# Detectielus_schema.net
KiCad netlist of a schematic drawn in EAGLE
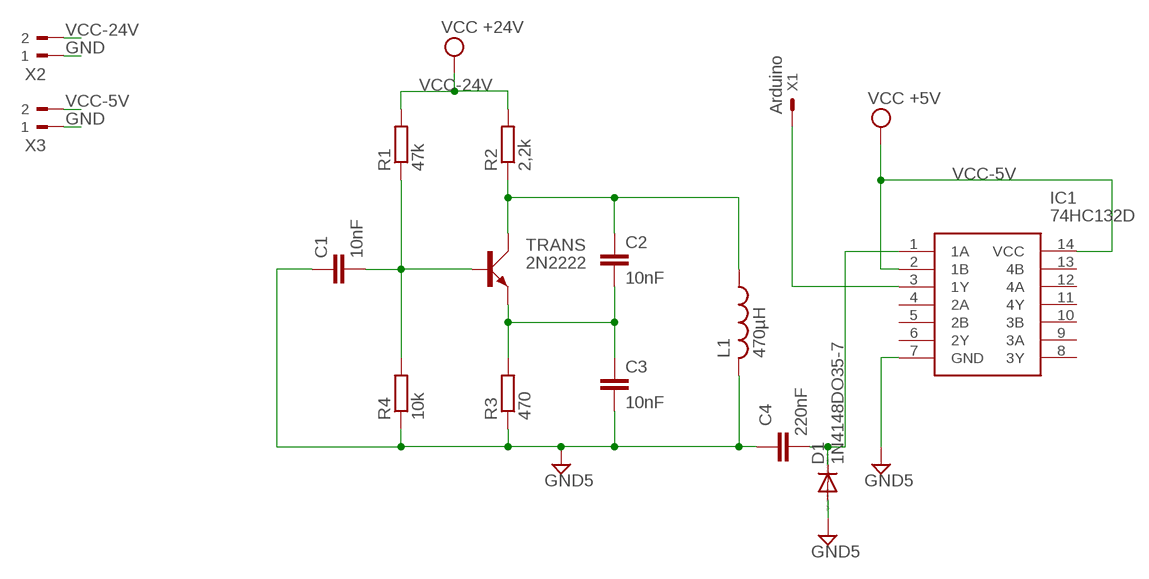
[diagram p0: schematic, sheet 1]

(export (version "E")
  (design (tool "Eeschema 10.0.6"))
  (components
    (comp (ref "C1")
      (value "10nF")
      (footprint "eagle-import:C050-024X044")
      (libsource (lib "eagle-import") (part "CAPACITOR"))
    )
    (comp (ref "C2")
      (value "10nF")
      (footprint "eagle-import:C050-024X044")
      (libsource (lib "eagle-import") (part "CAPACITOR"))
    )
    (comp (ref "C3")
      (value "10nF")
      (footprint "eagle-import:C050-024X044")
      (libsource (lib "eagle-import") (part "CAPACITOR"))
    )
    (comp (ref "C4")
      (value "220nF")
      (footprint "eagle-import:C050-024X044")
      (libsource (lib "eagle-import") (part "CAPACITOR"))
    )
    (comp (ref "D1")
      (value "1N4148DO35-7")
      (footprint "eagle-import:DO35-7")
      (libsource (lib "eagle-import") (part "1N4148DO35-7"))
    )
    (comp (ref "IC1")
      (value "74HC132D")
      (footprint "eagle-import:SOIC127P600X175-14N")
      (fields (field (name "RS_PART_NUMBER") "4367408"))
      (libsource (lib "eagle-import") (part "74HC132D"))
    )
    (comp (ref "L1")
      (value "470µH")
      (footprint "eagle-import:IR-4")
      (libsource (lib "eagle-import") (part "SPOEL"))
    )
    (comp (ref "R1")
      (value "47k")
      (footprint "eagle-import:RDH_15")
      (libsource (lib "eagle-import") (part "RESISTOR"))
    )
    (comp (ref "R2")
      (value "2,2k")
      (footprint "eagle-import:RDH_15")
      (libsource (lib "eagle-import") (part "RESISTOR"))
    )
    (comp (ref "R3")
      (value "470")
      (footprint "eagle-import:RDH_15")
      (libsource (lib "eagle-import") (part "RESISTOR"))
    )
    (comp (ref "R4")
      (value "10k")
      (footprint "eagle-import:RDH_15")
      (libsource (lib "eagle-import") (part "RESISTOR"))
    )
    (comp (ref "TRANS")
      (value "2N2222")
      (footprint "eagle-import:TO220AV")
      (libsource (lib "eagle-import") (part "TIP41C"))
    )
    (comp (ref "X1")
      (value "Arduino")
      (footprint "eagle-import:332-02")
      (libsource (lib "eagle-import") (part "332-02"))
    )
    (comp (ref "X2")
      (value "90-2")
      (footprint "eagle-import:90-2")
      (libsource (lib "eagle-import") (part "90-2"))
    )
    (comp (ref "X3")
      (value "90-2")
      (footprint "eagle-import:90-2")
      (libsource (lib "eagle-import") (part "90-2"))
    )
  )
  (nets
    (net (code "1") (name "/GND") (class "Default")
      (node (ref "X2") (pin "1") (pinfunction "1_1") (pintype "passive"))
      (node (ref "X3") (pin "1") (pinfunction "1_1") (pintype "passive"))
    )
    (net (code "2") (name "GND5") (class "Default")
      (node (ref "C1") (pin "1") (pinfunction "1_1") (pintype "passive"))
      (node (ref "C3") (pin "2") (pinfunction "2_2") (pintype "passive"))
      (node (ref "C4") (pin "1") (pinfunction "1_1") (pintype "passive"))
      (node (ref "D1") (pin "A") (pinfunction "A_A") (pintype "passive"))
      (node (ref "IC1") (pin "7") (pinfunction "GND_7") (pintype "power_in"))
      (node (ref "L1") (pin "2") (pinfunction "2_2") (pintype "passive"))
      (node (ref "R3") (pin "1") (pinfunction "1_1") (pintype "passive"))
      (node (ref "R4") (pin "1") (pinfunction "1_1") (pintype "passive"))
    )
    (net (code "3") (name "Net-(C1-Pad2)") (class "Default")
      (node (ref "C1") (pin "2") (pinfunction "2_2") (pintype "passive"))
      (node (ref "R1") (pin "1") (pinfunction "1_1") (pintype "passive"))
      (node (ref "R4") (pin "2") (pinfunction "2_2") (pintype "passive"))
      (node (ref "TRANS") (pin "B") (pinfunction "B_B") (pintype "passive"))
    )
    (net (code "4") (name "Net-(C2-Pad1)") (class "Default")
      (node (ref "C2") (pin "1") (pinfunction "1_1") (pintype "passive"))
      (node (ref "L1") (pin "1") (pinfunction "1_1") (pintype "passive"))
      (node (ref "R2") (pin "1") (pinfunction "1_1") (pintype "passive"))
      (node (ref "TRANS") (pin "C") (pinfunction "C_C") (pintype "passive"))
    )
    (net (code "5") (name "Net-(C2-Pad2)") (class "Default")
      (node (ref "C2") (pin "2") (pinfunction "2_2") (pintype "passive"))
      (node (ref "C3") (pin "1") (pinfunction "1_1") (pintype "passive"))
      (node (ref "R3") (pin "2") (pinfunction "2_2") (pintype "passive"))
      (node (ref "TRANS") (pin "E") (pinfunction "E_E") (pintype "passive"))
    )
    (net (code "6") (name "Net-(IC1-1A)") (class "Default")
      (node (ref "C4") (pin "2") (pinfunction "2_2") (pintype "passive"))
      (node (ref "D1") (pin "C") (pinfunction "C_C") (pintype "passive"))
      (node (ref "IC1") (pin "1") (pinfunction "1A_1") (pintype "bidirectional"))
    )
    (net (code "7") (name "Net-(IC1-1Y)") (class "Default")
      (node (ref "IC1") (pin "3") (pinfunction "1Y_3") (pintype "bidirectional"))
      (node (ref "X1") (pin "1") (pinfunction "S_1") (pintype "passive"))
    )
    (net (code "8") (name "VCC +5V") (class "Default")
      (node (ref "IC1") (pin "14") (pinfunction "VCC_14") (pintype "power_in"))
      (node (ref "IC1") (pin "2") (pinfunction "1B_2") (pintype "bidirectional"))
      (node (ref "X3") (pin "2") (pinfunction "2_2") (pintype "passive"))
    )
    (net (code "9") (name "VCC +24V") (class "Default")
      (node (ref "R1") (pin "2") (pinfunction "2_2") (pintype "passive"))
      (node (ref "R2") (pin "2") (pinfunction "2_2") (pintype "passive"))
      (node (ref "X2") (pin "2") (pinfunction "2_2") (pintype "passive"))
    )
    (net (code "10") (name "unconnected-(IC1-2A-Pad4)") (class "Default")
      (node (ref "IC1") (pin "4") (pinfunction "2A_4") (pintype "bidirectional"))
    )
    (net (code "11") (name "unconnected-(IC1-2B-Pad5)") (class "Default")
      (node (ref "IC1") (pin "5") (pinfunction "2B_5") (pintype "bidirectional"))
    )
    (net (code "12") (name "unconnected-(IC1-2Y-Pad6)") (class "Default")
      (node (ref "IC1") (pin "6") (pinfunction "2Y_6") (pintype "bidirectional"))
    )
    (net (code "13") (name "unconnected-(IC1-3A-Pad9)") (class "Default")
      (node (ref "IC1") (pin "9") (pinfunction "3A_9") (pintype "bidirectional"))
    )
    (net (code "14") (name "unconnected-(IC1-3B-Pad10)") (class "Default")
      (node (ref "IC1") (pin "10") (pinfunction "3B_10") (pintype "bidirectional"))
    )
    (net (code "15") (name "unconnected-(IC1-3Y-Pad8)") (class "Default")
      (node (ref "IC1") (pin "8") (pinfunction "3Y_8") (pintype "bidirectional"))
    )
    (net (code "16") (name "unconnected-(IC1-4A-Pad12)") (class "Default")
      (node (ref "IC1") (pin "12") (pinfunction "4A_12") (pintype "bidirectional"))
    )
    (net (code "17") (name "unconnected-(IC1-4B-Pad13)") (class "Default")
      (node (ref "IC1") (pin "13") (pinfunction "4B_13") (pintype "bidirectional"))
    )
    (net (code "18") (name "unconnected-(IC1-4Y-Pad11)") (class "Default")
      (node (ref "IC1") (pin "11") (pinfunction "4Y_11") (pintype "bidirectional"))
    )
  )
)
